# thucthi.net
KiCad netlist of a schematic drawn in Altium Designer
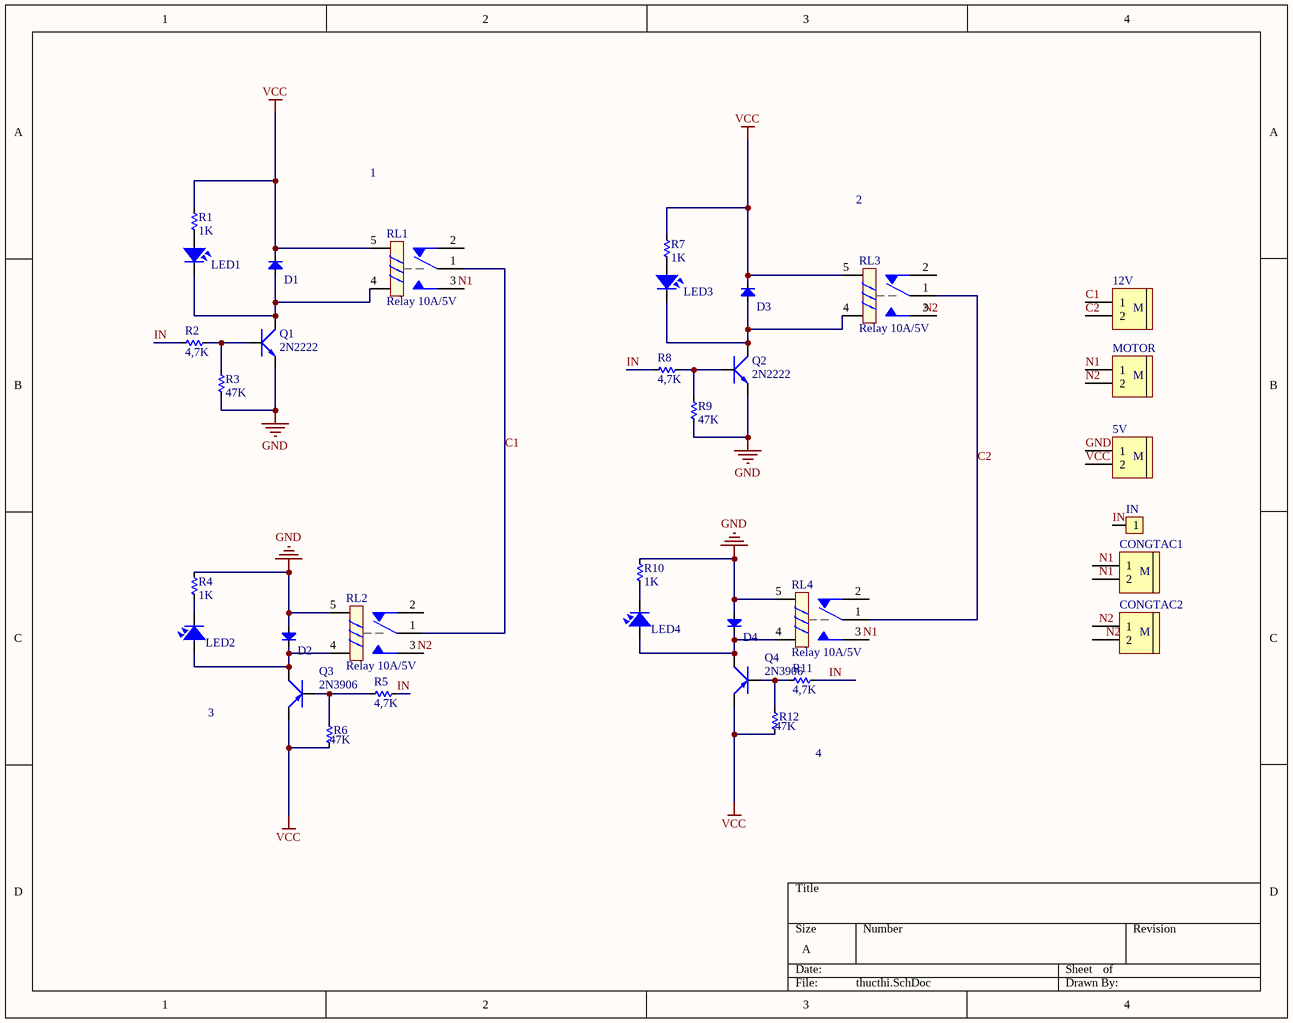
[diagram p0: thucthi.SchDoc]

(export (version "E")
  (design (tool "Eeschema 10.0.6"))
  (components
    (comp (ref "5V")
      (value "Header 2 - M")
      (footprint "Medium - Header 2")
      (description "Header, 2-Pin, Medium")
      (fields (field (name "PUBLISHER") "Altium Limited"))
      (libsource (lib "Schematic") (part "Header 2 - M"))
    )
    (comp (ref "12V")
      (value "Header 2 - M")
      (footprint "Medium - Header 2")
      (description "Header, 2-Pin, Medium")
      (fields (field (name "PUBLISHER") "Altium Limited"))
      (libsource (lib "Schematic") (part "Header 2 - M"))
    )
    (comp (ref "CONGTAC1")
      (value "Header 2 - M")
      (footprint "Medium - Header 2")
      (description "Header, 2-Pin, Medium")
      (fields (field (name "PUBLISHER") "Altium Limited"))
      (libsource (lib "Schematic") (part "Header 2 - M"))
    )
    (comp (ref "CONGTAC2")
      (value "Header 2 - M")
      (footprint "Medium - Header 2")
      (description "Header, 2-Pin, Medium")
      (fields (field (name "PUBLISHER") "Altium Limited"))
      (libsource (lib "Schematic") (part "Header 2 - M"))
    )
    (comp (ref "D1")
      (value "Diode")
      (footprint "DIO-1A")
      (description "Default Diode")
      (fields (field (name "PUBLISHER") "Altium Limited"))
      (libsource (lib "Altium Library") (part "Diode"))
    )
    (comp (ref "D2")
      (value "Diode")
      (footprint "DIO-1A")
      (description "Default Diode")
      (fields (field (name "PUBLISHER") "Altium Limited"))
      (libsource (lib "Altium Library") (part "Diode"))
    )
    (comp (ref "D3")
      (value "Diode")
      (footprint "DIO-1A")
      (description "Default Diode")
      (fields (field (name "PUBLISHER") "Altium Limited"))
      (libsource (lib "Altium Library") (part "Diode"))
    )
    (comp (ref "D4")
      (value "Diode")
      (footprint "DIO-1A")
      (description "Default Diode")
      (fields (field (name "PUBLISHER") "Altium Limited"))
      (libsource (lib "Altium Library") (part "Diode"))
    )
    (comp (ref "IN")
      (value "JP1")
      (footprint "JP1-D1T")
      (description "WR-PHD 2.54 mm Angled Socket Header")
      (fields
        (field (name "MANUFACTURER") "Würth Elektronik eiSos GmbH")
        (field (name "PARTNO") "613002143121")
        (field (name "CREATED BY") "Karrer Zheng")
      )
      (libsource (lib "Altium Library") (part "JP1"))
    )
    (comp (ref "LED1")
      (value "LED")
      (footprint "LED-5-RED")
      (description "LED Single colour Green and Red")
      (libsource (lib "Altium Library") (part "LED"))
    )
    (comp (ref "LED2")
      (value "LED")
      (footprint "LED-5-Green")
      (description "LED Single colour Green and Red")
      (libsource (lib "Altium Library") (part "LED"))
    )
    (comp (ref "LED3")
      (value "LED")
      (footprint "LED-5-RED")
      (description "LED Single colour Green and Red")
      (libsource (lib "Altium Library") (part "LED"))
    )
    (comp (ref "LED4")
      (value "LED")
      (footprint "LED-5-Green")
      (description "LED Single colour Green and Red")
      (libsource (lib "Altium Library") (part "LED"))
    )
    (comp (ref "MOTOR")
      (value "Header 2 - M")
      (footprint "Medium - Header 2")
      (description "Header, 2-Pin, Medium")
      (fields (field (name "PUBLISHER") "Altium Limited"))
      (libsource (lib "Schematic") (part "Header 2 - M"))
    )
    (comp (ref "Q1")
      (value "2N2222")
      (footprint "TO92-123")
      (description "NPN 600mW, ECB")
      (libsource (lib "Altium Library") (part "2N222"))
    )
    (comp (ref "Q2")
      (value "2N2222")
      (footprint "TO92-123")
      (description "NPN 600mW, ECB")
      (libsource (lib "Altium Library") (part "2N222"))
    )
    (comp (ref "Q3")
      (value "2N3906")
      (footprint "TO92-123")
      (description "PNP 600mW, ECB")
      (libsource (lib "Altium Library") (part "2N3906"))
    )
    (comp (ref "Q4")
      (value "2N3906")
      (footprint "TO92-123")
      (description "PNP 600mW, ECB")
      (libsource (lib "Altium Library") (part "2N3906"))
    )
    (comp (ref "R1")
      (value "1K")
      (footprint "RES-1/2W")
      (description "Res")
      (fields
        (field (name "MANUFACTURER") "Generic Components")
        (field (name "PUBLISHER") "Altium Hobart Technology Centre")
      )
      (libsource (lib "Altium Library") (part "Res"))
    )
    (comp (ref "R2")
      (value "4,7K")
      (footprint "RES-1/2W")
      (description "Res")
      (fields
        (field (name "MANUFACTURER") "Generic Components")
        (field (name "PUBLISHER") "Altium Hobart Technology Centre")
      )
      (libsource (lib "Altium Library") (part "Res"))
    )
    (comp (ref "R3")
      (value "47K")
      (footprint "RES-1/2W")
      (description "Res")
      (fields
        (field (name "MANUFACTURER") "Generic Components")
        (field (name "PUBLISHER") "Altium Hobart Technology Centre")
      )
      (libsource (lib "Altium Library") (part "Res"))
    )
    (comp (ref "R4")
      (value "1K")
      (footprint "RES-1/2W")
      (description "Res")
      (fields
        (field (name "MANUFACTURER") "Generic Components")
        (field (name "PUBLISHER") "Altium Hobart Technology Centre")
      )
      (libsource (lib "Altium Library") (part "Res"))
    )
    (comp (ref "R5")
      (value "4,7K")
      (footprint "RES-1/2W")
      (description "Res")
      (fields
        (field (name "MANUFACTURER") "Generic Components")
        (field (name "PUBLISHER") "Altium Hobart Technology Centre")
      )
      (libsource (lib "Altium Library") (part "Res"))
    )
    (comp (ref "R6")
      (value "47K")
      (footprint "RES-1/2W")
      (description "Res")
      (fields
        (field (name "MANUFACTURER") "Generic Components")
        (field (name "PUBLISHER") "Altium Hobart Technology Centre")
      )
      (libsource (lib "Altium Library") (part "Res"))
    )
    (comp (ref "R7")
      (value "1K")
      (footprint "RES-1/2W")
      (description "Res")
      (fields
        (field (name "MANUFACTURER") "Generic Components")
        (field (name "PUBLISHER") "Altium Hobart Technology Centre")
      )
      (libsource (lib "Altium Library") (part "Res"))
    )
    (comp (ref "R8")
      (value "4,7K")
      (footprint "RES-1/2W")
      (description "Res")
      (fields
        (field (name "MANUFACTURER") "Generic Components")
        (field (name "PUBLISHER") "Altium Hobart Technology Centre")
      )
      (libsource (lib "Altium Library") (part "Res"))
    )
    (comp (ref "R9")
      (value "47K")
      (footprint "RES-1/2W")
      (description "Res")
      (fields
        (field (name "MANUFACTURER") "Generic Components")
        (field (name "PUBLISHER") "Altium Hobart Technology Centre")
      )
      (libsource (lib "Altium Library") (part "Res"))
    )
    (comp (ref "R10")
      (value "1K")
      (footprint "RES-1/2W")
      (description "Res")
      (fields
        (field (name "MANUFACTURER") "Generic Components")
        (field (name "PUBLISHER") "Altium Hobart Technology Centre")
      )
      (libsource (lib "Altium Library") (part "Res"))
    )
    (comp (ref "R11")
      (value "4,7K")
      (footprint "RES-1/2W")
      (description "Res")
      (fields
        (field (name "MANUFACTURER") "Generic Components")
        (field (name "PUBLISHER") "Altium Hobart Technology Centre")
      )
      (libsource (lib "Altium Library") (part "Res"))
    )
    (comp (ref "R12")
      (value "47K")
      (footprint "RES-1/2W")
      (description "Res")
      (fields
        (field (name "MANUFACTURER") "Generic Components")
        (field (name "PUBLISHER") "Altium Hobart Technology Centre")
      )
      (libsource (lib "Altium Library") (part "Res"))
    )
    (comp (ref "RL1")
      (value "Relay 10A/5V")
      (footprint "RELAY 5")
      (description "Relay SPDT,10A - 12VDC 5 Pin")
      (libsource (lib "Altium Library") (part "Relay 5"))
    )
    (comp (ref "RL2")
      (value "Relay 10A/5V")
      (footprint "RELAY 5")
      (description "Relay SPDT,10A - 12VDC 5 Pin")
      (libsource (lib "Altium Library") (part "Relay 5"))
    )
    (comp (ref "RL3")
      (value "Relay 10A/5V")
      (footprint "RELAY 5")
      (description "Relay SPDT,10A - 12VDC 5 Pin")
      (libsource (lib "Altium Library") (part "Relay 5"))
    )
    (comp (ref "RL4")
      (value "Relay 10A/5V")
      (footprint "RELAY 5")
      (description "Relay SPDT,10A - 12VDC 5 Pin")
      (libsource (lib "Altium Library") (part "Relay 5"))
    )
  )
  (nets
    (net (code "2") (name "/C1") (class "Default")
      (node (ref "12V") (pin "1") (pinfunction "1_1") (pintype "passive"))
      (node (ref "RL1") (pin "1") (pinfunction "1_1") (pintype "passive"))
      (node (ref "RL2") (pin "1") (pinfunction "1_1") (pintype "passive"))
    )
    (net (code "3") (name "/C2") (class "Default")
      (node (ref "12V") (pin "2") (pinfunction "2_2") (pintype "passive"))
      (node (ref "RL3") (pin "1") (pinfunction "1_1") (pintype "passive"))
      (node (ref "RL4") (pin "1") (pinfunction "1_1") (pintype "passive"))
    )
    (net (code "4") (name "/IN") (class "Default")
      (node (ref "IN") (pin "1") (pinfunction "1_1") (pintype "passive"))
      (node (ref "R11") (pin "2") (pinfunction "2_2") (pintype "passive"))
      (node (ref "R2") (pin "2") (pinfunction "2_2") (pintype "passive"))
      (node (ref "R5") (pin "2") (pinfunction "2_2") (pintype "passive"))
      (node (ref "R8") (pin "2") (pinfunction "2_2") (pintype "passive"))
    )
    (net (code "5") (name "/N1") (class "Default")
      (node (ref "MOTOR") (pin "1") (pinfunction "1_1") (pintype "passive"))
    )
    (net (code "6") (name "/N2") (class "Default")
      (node (ref "MOTOR") (pin "2") (pinfunction "2_2") (pintype "passive"))
    )
    (net (code "7") (name "GND") (class "Default")
      (node (ref "5V") (pin "1") (pinfunction "1_1") (pintype "passive"))
      (node (ref "D2") (pin "1") (pinfunction "A_1") (pintype "passive"))
      (node (ref "D4") (pin "1") (pinfunction "A_1") (pintype "passive"))
      (node (ref "Q1") (pin "1") (pinfunction "E_1") (pintype "passive"))
      (node (ref "Q2") (pin "1") (pinfunction "E_1") (pintype "passive"))
      (node (ref "R10") (pin "2") (pinfunction "2_2") (pintype "passive"))
      (node (ref "R3") (pin "1") (pinfunction "1_1") (pintype "passive"))
      (node (ref "R4") (pin "2") (pinfunction "2_2") (pintype "passive"))
      (node (ref "R9") (pin "1") (pinfunction "1_1") (pintype "passive"))
      (node (ref "RL2") (pin "5") (pinfunction "5_5") (pintype "passive"))
      (node (ref "RL4") (pin "5") (pinfunction "5_5") (pintype "passive"))
    )
    (net (code "8") (name "Net-(D1-A)") (class "Default")
      (node (ref "D1") (pin "1") (pinfunction "A_1") (pintype "passive"))
      (node (ref "LED1") (pin "2") (pinfunction "2_2") (pintype "passive"))
      (node (ref "Q1") (pin "3") (pinfunction "C_3") (pintype "passive"))
      (node (ref "RL1") (pin "4") (pinfunction "4_4") (pintype "passive"))
    )
    (net (code "9") (name "Net-(D2-K)") (class "Default")
      (node (ref "D2") (pin "2") (pinfunction "K_2") (pintype "passive"))
      (node (ref "LED2") (pin "1") (pinfunction "1_1") (pintype "passive"))
      (node (ref "Q3") (pin "3") (pinfunction "C_3") (pintype "passive"))
      (node (ref "RL2") (pin "4") (pinfunction "4_4") (pintype "passive"))
    )
    (net (code "10") (name "Net-(D3-A)") (class "Default")
      (node (ref "D3") (pin "1") (pinfunction "A_1") (pintype "passive"))
      (node (ref "LED3") (pin "2") (pinfunction "2_2") (pintype "passive"))
      (node (ref "Q2") (pin "3") (pinfunction "C_3") (pintype "passive"))
      (node (ref "RL3") (pin "4") (pinfunction "4_4") (pintype "passive"))
    )
    (net (code "11") (name "Net-(D4-K)") (class "Default")
      (node (ref "D4") (pin "2") (pinfunction "K_2") (pintype "passive"))
      (node (ref "LED4") (pin "1") (pinfunction "1_1") (pintype "passive"))
      (node (ref "Q4") (pin "3") (pinfunction "C_3") (pintype "passive"))
      (node (ref "RL4") (pin "4") (pinfunction "4_4") (pintype "passive"))
    )
    (net (code "12") (name "Net-(LED1-Pad1)") (class "Default")
      (node (ref "LED1") (pin "1") (pinfunction "1_1") (pintype "passive"))
      (node (ref "R1") (pin "1") (pinfunction "1_1") (pintype "passive"))
    )
    (net (code "13") (name "Net-(LED2-Pad2)") (class "Default")
      (node (ref "LED2") (pin "2") (pinfunction "2_2") (pintype "passive"))
      (node (ref "R4") (pin "1") (pinfunction "1_1") (pintype "passive"))
    )
    (net (code "14") (name "Net-(LED3-Pad1)") (class "Default")
      (node (ref "LED3") (pin "1") (pinfunction "1_1") (pintype "passive"))
      (node (ref "R7") (pin "1") (pinfunction "1_1") (pintype "passive"))
    )
    (net (code "15") (name "Net-(LED4-Pad2)") (class "Default")
      (node (ref "LED4") (pin "2") (pinfunction "2_2") (pintype "passive"))
      (node (ref "R10") (pin "1") (pinfunction "1_1") (pintype "passive"))
    )
    (net (code "16") (name "Net-(Q1-B)") (class "Default")
      (node (ref "Q1") (pin "2") (pinfunction "B_2") (pintype "passive"))
      (node (ref "R2") (pin "1") (pinfunction "1_1") (pintype "passive"))
      (node (ref "R3") (pin "2") (pinfunction "2_2") (pintype "passive"))
    )
    (net (code "17") (name "Net-(Q2-B)") (class "Default")
      (node (ref "Q2") (pin "2") (pinfunction "B_2") (pintype "passive"))
      (node (ref "R8") (pin "1") (pinfunction "1_1") (pintype "passive"))
      (node (ref "R9") (pin "2") (pinfunction "2_2") (pintype "passive"))
    )
    (net (code "18") (name "Net-(Q3-B)") (class "Default")
      (node (ref "Q3") (pin "2") (pinfunction "B_2") (pintype "passive"))
      (node (ref "R5") (pin "1") (pinfunction "1_1") (pintype "passive"))
      (node (ref "R6") (pin "2") (pinfunction "2_2") (pintype "passive"))
    )
    (net (code "19") (name "Net-(Q4-B)") (class "Default")
      (node (ref "Q4") (pin "2") (pinfunction "B_2") (pintype "passive"))
      (node (ref "R11") (pin "1") (pinfunction "1_1") (pintype "passive"))
      (node (ref "R12") (pin "2") (pinfunction "2_2") (pintype "passive"))
    )
    (net (code "20") (name "VCC") (class "Default")
      (node (ref "5V") (pin "2") (pinfunction "2_2") (pintype "passive"))
      (node (ref "D1") (pin "2") (pinfunction "K_2") (pintype "passive"))
      (node (ref "D3") (pin "2") (pinfunction "K_2") (pintype "passive"))
      (node (ref "Q3") (pin "1") (pinfunction "E_1") (pintype "passive"))
      (node (ref "Q4") (pin "1") (pinfunction "E_1") (pintype "passive"))
      (node (ref "R1") (pin "2") (pinfunction "2_2") (pintype "passive"))
      (node (ref "R12") (pin "1") (pinfunction "1_1") (pintype "passive"))
      (node (ref "R6") (pin "1") (pinfunction "1_1") (pintype "passive"))
      (node (ref "R7") (pin "2") (pinfunction "2_2") (pintype "passive"))
      (node (ref "RL1") (pin "5") (pinfunction "5_5") (pintype "passive"))
      (node (ref "RL3") (pin "5") (pinfunction "5_5") (pintype "passive"))
    )
    (net (code "21") (name "unconnected-(CONGTAC1-Pad1)") (class "Default")
      (node (ref "CONGTAC1") (pin "1") (pinfunction "1_1") (pintype "passive"))
    )
    (net (code "22") (name "unconnected-(CONGTAC1-Pad2)") (class "Default")
      (node (ref "CONGTAC1") (pin "2") (pinfunction "2_2") (pintype "passive"))
    )
    (net (code "23") (name "unconnected-(CONGTAC2-Pad1)") (class "Default")
      (node (ref "CONGTAC2") (pin "1") (pinfunction "1_1") (pintype "passive"))
    )
    (net (code "24") (name "unconnected-(CONGTAC2-Pad2)") (class "Default")
      (node (ref "CONGTAC2") (pin "2") (pinfunction "2_2") (pintype "passive"))
    )
    (net (code "25") (name "unconnected-(RL1-Pad2)") (class "Default")
      (node (ref "RL1") (pin "2") (pinfunction "2_2") (pintype "passive"))
    )
    (net (code "26") (name "unconnected-(RL1-Pad3)") (class "Default")
      (node (ref "RL1") (pin "3") (pinfunction "3_3") (pintype "passive"))
    )
    (net (code "27") (name "unconnected-(RL2-Pad2)") (class "Default")
      (node (ref "RL2") (pin "2") (pinfunction "2_2") (pintype "passive"))
    )
    (net (code "28") (name "unconnected-(RL2-Pad3)") (class "Default")
      (node (ref "RL2") (pin "3") (pinfunction "3_3") (pintype "passive"))
    )
    (net (code "29") (name "unconnected-(RL3-Pad2)") (class "Default")
      (node (ref "RL3") (pin "2") (pinfunction "2_2") (pintype "passive"))
    )
    (net (code "30") (name "unconnected-(RL3-Pad3)") (class "Default")
      (node (ref "RL3") (pin "3") (pinfunction "3_3") (pintype "passive"))
    )
    (net (code "31") (name "unconnected-(RL4-Pad2)") (class "Default")
      (node (ref "RL4") (pin "2") (pinfunction "2_2") (pintype "passive"))
    )
    (net (code "32") (name "unconnected-(RL4-Pad3)") (class "Default")
      (node (ref "RL4") (pin "3") (pinfunction "3_3") (pintype "passive"))
    )
  )
)
